# 04_MCU_Part.net
KiCad netlist of a schematic drawn in Altium Designer
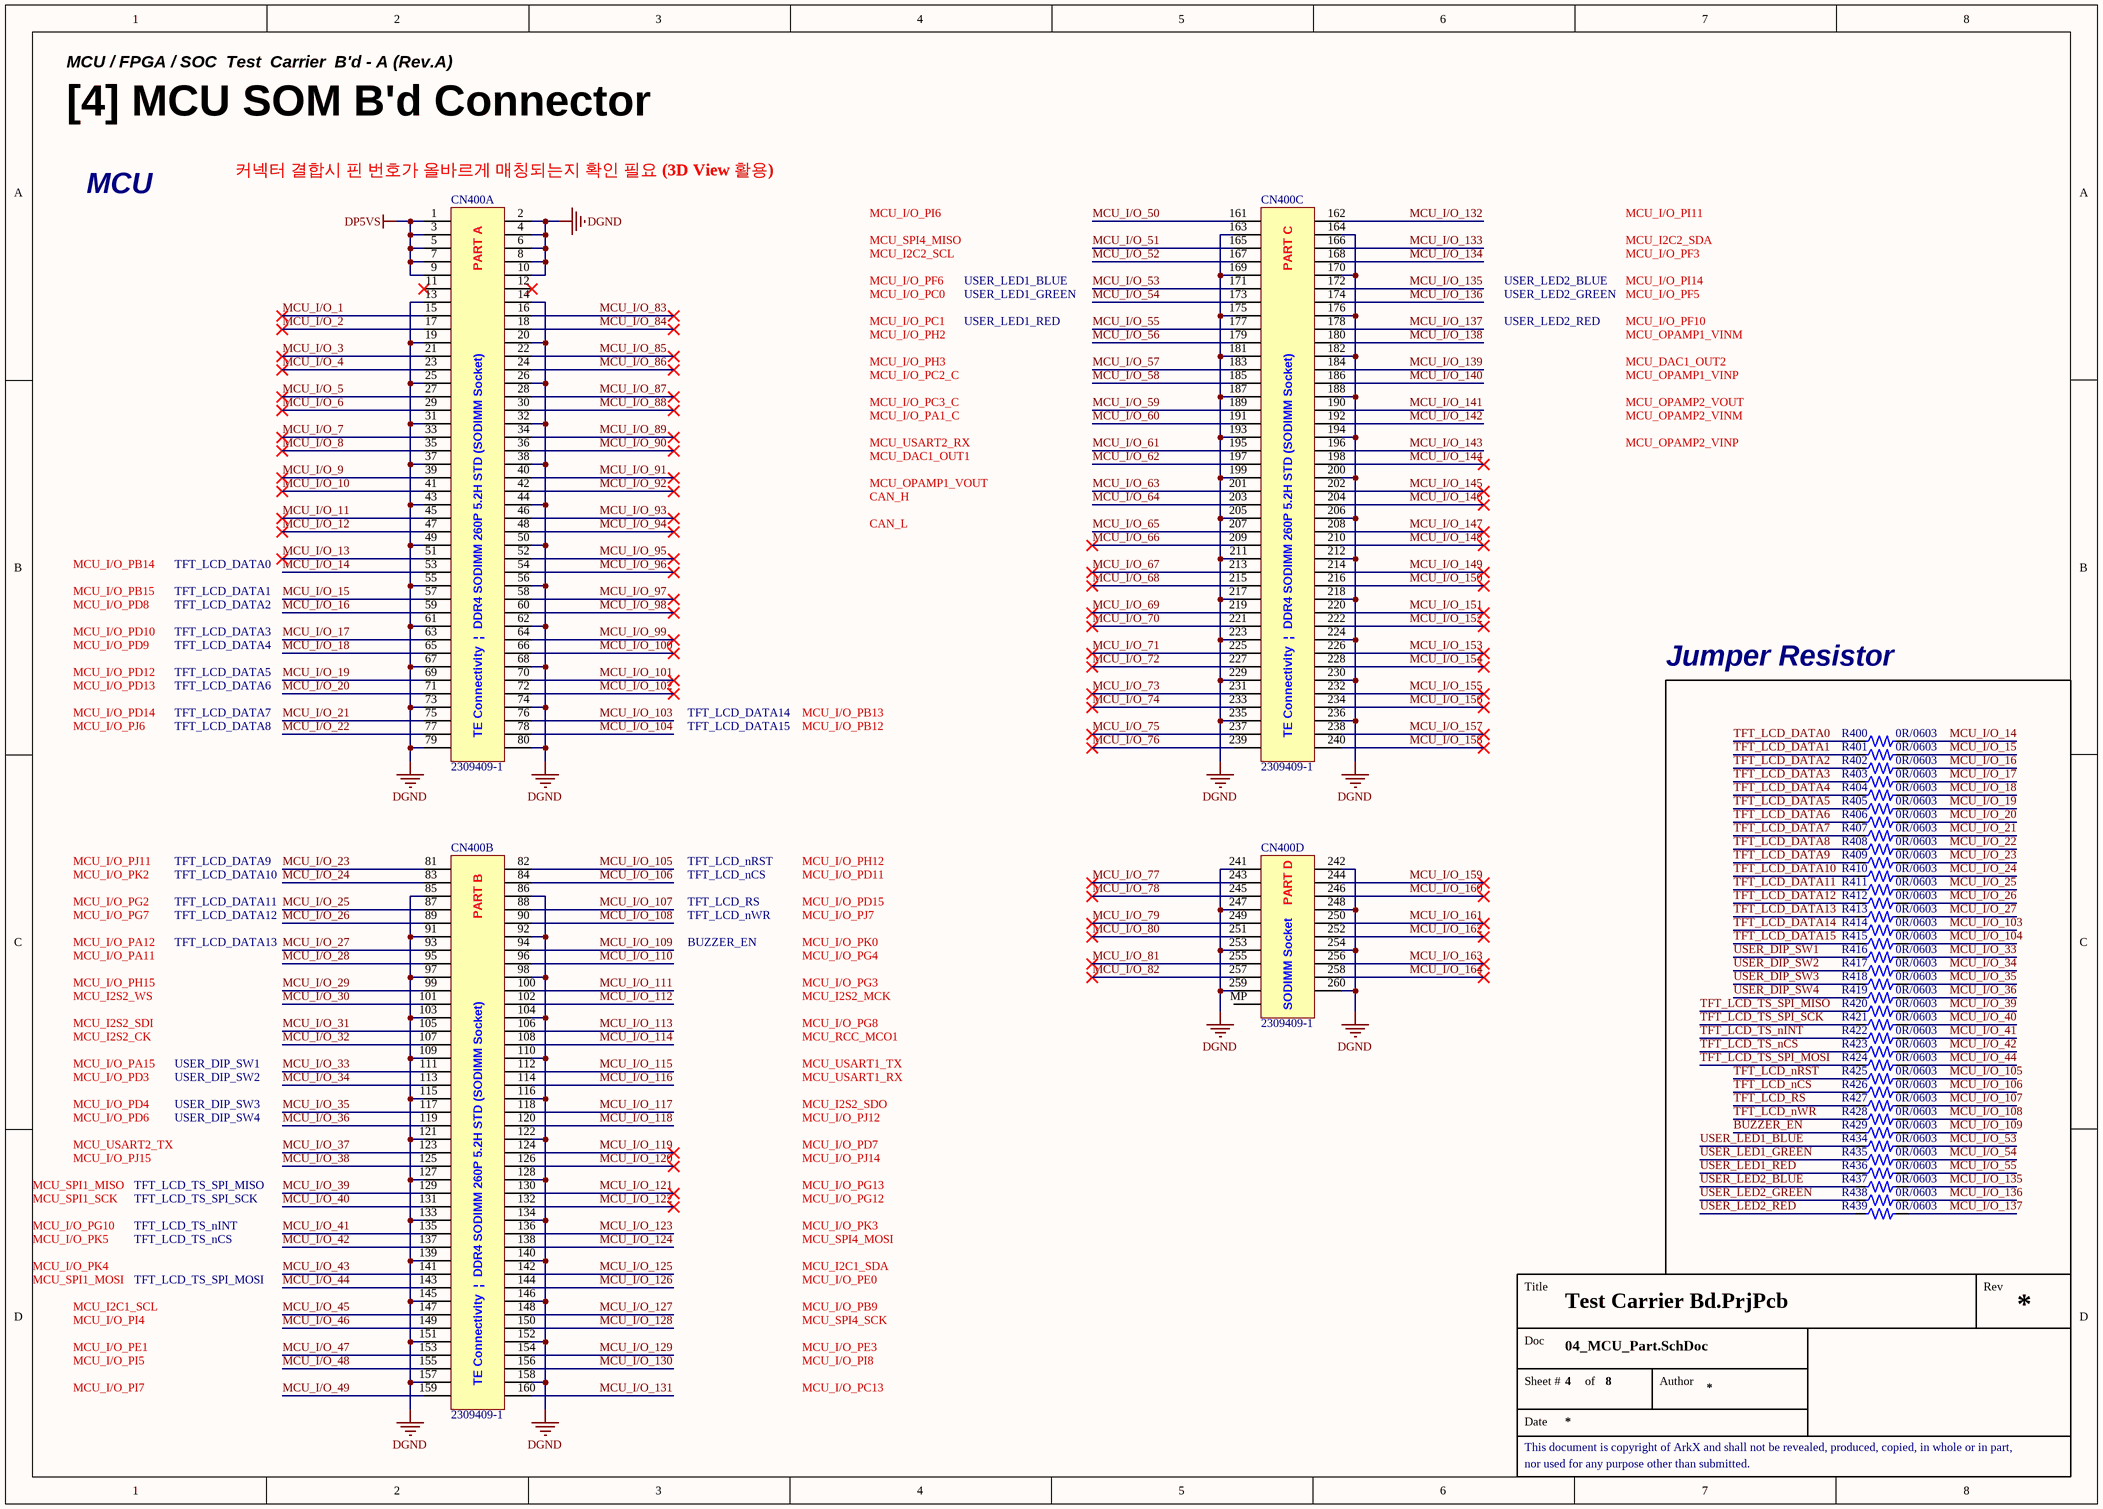
[diagram p0: 04_MCU_Part.SchDoc]

(export (version "E")
  (design (tool "Eeschema 10.0.6"))
  (components
    (comp (ref "CN400")
      (value "2309409-1")
      (footprint "CON_SODIMM_2309409-1")
      (fields (field (name "MANUFACTURER") "TE Connectivity") (field (name "LCSC PART #") "C5164025"))
      (libsource (lib "Arkx") (part "CON_SODIMM_2309409-1"))
    )
    (comp (ref "R400")
      (value "0R/0603")
      (footprint "RES 0603 (0201_inch)")
      (description "50mW Thick Film Resistors 25V ±1% 0Ω 0201  Chip Resistor - Surface Mount ROHS")
      (fields (field (name "LCSC PART #") "C106227"))
      (libsource (lib "Arkx") (part "RES_0R/0603/50mW"))
    )
    (comp (ref "R401")
      (value "0R/0603")
      (footprint "RES 0603 (0201_inch)")
      (description "50mW Thick Film Resistors 25V ±1% 0Ω 0201  Chip Resistor - Surface Mount ROHS")
      (fields (field (name "LCSC PART #") "C106227"))
      (libsource (lib "Arkx") (part "RES_0R/0603/50mW"))
    )
    (comp (ref "R402")
      (value "0R/0603")
      (footprint "RES 0603 (0201_inch)")
      (description "50mW Thick Film Resistors 25V ±1% 0Ω 0201  Chip Resistor - Surface Mount ROHS")
      (fields (field (name "LCSC PART #") "C106227"))
      (libsource (lib "Arkx") (part "RES_0R/0603/50mW"))
    )
    (comp (ref "R403")
      (value "0R/0603")
      (footprint "RES 0603 (0201_inch)")
      (description "50mW Thick Film Resistors 25V ±1% 0Ω 0201  Chip Resistor - Surface Mount ROHS")
      (fields (field (name "LCSC PART #") "C106227"))
      (libsource (lib "Arkx") (part "RES_0R/0603/50mW"))
    )
    (comp (ref "R404")
      (value "0R/0603")
      (footprint "RES 0603 (0201_inch)")
      (description "50mW Thick Film Resistors 25V ±1% 0Ω 0201  Chip Resistor - Surface Mount ROHS")
      (fields (field (name "LCSC PART #") "C106227"))
      (libsource (lib "Arkx") (part "RES_0R/0603/50mW"))
    )
    (comp (ref "R405")
      (value "0R/0603")
      (footprint "RES 0603 (0201_inch)")
      (description "50mW Thick Film Resistors 25V ±1% 0Ω 0201  Chip Resistor - Surface Mount ROHS")
      (fields (field (name "LCSC PART #") "C106227"))
      (libsource (lib "Arkx") (part "RES_0R/0603/50mW"))
    )
    (comp (ref "R406")
      (value "0R/0603")
      (footprint "RES 0603 (0201_inch)")
      (description "50mW Thick Film Resistors 25V ±1% 0Ω 0201  Chip Resistor - Surface Mount ROHS")
      (fields (field (name "LCSC PART #") "C106227"))
      (libsource (lib "Arkx") (part "RES_0R/0603/50mW"))
    )
    (comp (ref "R407")
      (value "0R/0603")
      (footprint "RES 0603 (0201_inch)")
      (description "50mW Thick Film Resistors 25V ±1% 0Ω 0201  Chip Resistor - Surface Mount ROHS")
      (fields (field (name "LCSC PART #") "C106227"))
      (libsource (lib "Arkx") (part "RES_0R/0603/50mW"))
    )
    (comp (ref "R408")
      (value "0R/0603")
      (footprint "RES 0603 (0201_inch)")
      (description "50mW Thick Film Resistors 25V ±1% 0Ω 0201  Chip Resistor - Surface Mount ROHS")
      (fields (field (name "LCSC PART #") "C106227"))
      (libsource (lib "Arkx") (part "RES_0R/0603/50mW"))
    )
    (comp (ref "R409")
      (value "0R/0603")
      (footprint "RES 0603 (0201_inch)")
      (description "50mW Thick Film Resistors 25V ±1% 0Ω 0201  Chip Resistor - Surface Mount ROHS")
      (fields (field (name "LCSC PART #") "C106227"))
      (libsource (lib "Arkx") (part "RES_0R/0603/50mW"))
    )
    (comp (ref "R410")
      (value "0R/0603")
      (footprint "RES 0603 (0201_inch)")
      (description "50mW Thick Film Resistors 25V ±1% 0Ω 0201  Chip Resistor - Surface Mount ROHS")
      (fields (field (name "LCSC PART #") "C106227"))
      (libsource (lib "Arkx") (part "RES_0R/0603/50mW"))
    )
    (comp (ref "R411")
      (value "0R/0603")
      (footprint "RES 0603 (0201_inch)")
      (description "50mW Thick Film Resistors 25V ±1% 0Ω 0201  Chip Resistor - Surface Mount ROHS")
      (fields (field (name "LCSC PART #") "C106227"))
      (libsource (lib "Arkx") (part "RES_0R/0603/50mW"))
    )
    (comp (ref "R412")
      (value "0R/0603")
      (footprint "RES 0603 (0201_inch)")
      (description "50mW Thick Film Resistors 25V ±1% 0Ω 0201  Chip Resistor - Surface Mount ROHS")
      (fields (field (name "LCSC PART #") "C106227"))
      (libsource (lib "Arkx") (part "RES_0R/0603/50mW"))
    )
    (comp (ref "R413")
      (value "0R/0603")
      (footprint "RES 0603 (0201_inch)")
      (description "50mW Thick Film Resistors 25V ±1% 0Ω 0201  Chip Resistor - Surface Mount ROHS")
      (fields (field (name "LCSC PART #") "C106227"))
      (libsource (lib "Arkx") (part "RES_0R/0603/50mW"))
    )
    (comp (ref "R414")
      (value "0R/0603")
      (footprint "RES 0603 (0201_inch)")
      (description "50mW Thick Film Resistors 25V ±1% 0Ω 0201  Chip Resistor - Surface Mount ROHS")
      (fields (field (name "LCSC PART #") "C106227"))
      (libsource (lib "Arkx") (part "RES_0R/0603/50mW"))
    )
    (comp (ref "R415")
      (value "0R/0603")
      (footprint "RES 0603 (0201_inch)")
      (description "50mW Thick Film Resistors 25V ±1% 0Ω 0201  Chip Resistor - Surface Mount ROHS")
      (fields (field (name "LCSC PART #") "C106227"))
      (libsource (lib "Arkx") (part "RES_0R/0603/50mW"))
    )
    (comp (ref "R416")
      (value "0R/0603")
      (footprint "RES 0603 (0201_inch)")
      (description "50mW Thick Film Resistors 25V ±1% 0Ω 0201  Chip Resistor - Surface Mount ROHS")
      (fields (field (name "LCSC PART #") "C106227"))
      (libsource (lib "Arkx") (part "RES_0R/0603/50mW"))
    )
    (comp (ref "R417")
      (value "0R/0603")
      (footprint "RES 0603 (0201_inch)")
      (description "50mW Thick Film Resistors 25V ±1% 0Ω 0201  Chip Resistor - Surface Mount ROHS")
      (fields (field (name "LCSC PART #") "C106227"))
      (libsource (lib "Arkx") (part "RES_0R/0603/50mW"))
    )
    (comp (ref "R418")
      (value "0R/0603")
      (footprint "RES 0603 (0201_inch)")
      (description "50mW Thick Film Resistors 25V ±1% 0Ω 0201  Chip Resistor - Surface Mount ROHS")
      (fields (field (name "LCSC PART #") "C106227"))
      (libsource (lib "Arkx") (part "RES_0R/0603/50mW"))
    )
    (comp (ref "R419")
      (value "0R/0603")
      (footprint "RES 0603 (0201_inch)")
      (description "50mW Thick Film Resistors 25V ±1% 0Ω 0201  Chip Resistor - Surface Mount ROHS")
      (fields (field (name "LCSC PART #") "C106227"))
      (libsource (lib "Arkx") (part "RES_0R/0603/50mW"))
    )
    (comp (ref "R420")
      (value "0R/0603")
      (footprint "RES 0603 (0201_inch)")
      (description "50mW Thick Film Resistors 25V ±1% 0Ω 0201  Chip Resistor - Surface Mount ROHS")
      (fields (field (name "LCSC PART #") "C106227"))
      (libsource (lib "Arkx") (part "RES_0R/0603/50mW"))
    )
    (comp (ref "R421")
      (value "0R/0603")
      (footprint "RES 0603 (0201_inch)")
      (description "50mW Thick Film Resistors 25V ±1% 0Ω 0201  Chip Resistor - Surface Mount ROHS")
      (fields (field (name "LCSC PART #") "C106227"))
      (libsource (lib "Arkx") (part "RES_0R/0603/50mW"))
    )
    (comp (ref "R422")
      (value "0R/0603")
      (footprint "RES 0603 (0201_inch)")
      (description "50mW Thick Film Resistors 25V ±1% 0Ω 0201  Chip Resistor - Surface Mount ROHS")
      (fields (field (name "LCSC PART #") "C106227"))
      (libsource (lib "Arkx") (part "RES_0R/0603/50mW"))
    )
    (comp (ref "R423")
      (value "0R/0603")
      (footprint "RES 0603 (0201_inch)")
      (description "50mW Thick Film Resistors 25V ±1% 0Ω 0201  Chip Resistor - Surface Mount ROHS")
      (fields (field (name "LCSC PART #") "C106227"))
      (libsource (lib "Arkx") (part "RES_0R/0603/50mW"))
    )
    (comp (ref "R424")
      (value "0R/0603")
      (footprint "RES 0603 (0201_inch)")
      (description "50mW Thick Film Resistors 25V ±1% 0Ω 0201  Chip Resistor - Surface Mount ROHS")
      (fields (field (name "LCSC PART #") "C106227"))
      (libsource (lib "Arkx") (part "RES_0R/0603/50mW"))
    )
    (comp (ref "R425")
      (value "0R/0603")
      (footprint "RES 0603 (0201_inch)")
      (description "50mW Thick Film Resistors 25V ±1% 0Ω 0201  Chip Resistor - Surface Mount ROHS")
      (fields (field (name "LCSC PART #") "C106227"))
      (libsource (lib "Arkx") (part "RES_0R/0603/50mW"))
    )
    (comp (ref "R426")
      (value "0R/0603")
      (footprint "RES 0603 (0201_inch)")
      (description "50mW Thick Film Resistors 25V ±1% 0Ω 0201  Chip Resistor - Surface Mount ROHS")
      (fields (field (name "LCSC PART #") "C106227"))
      (libsource (lib "Arkx") (part "RES_0R/0603/50mW"))
    )
    (comp (ref "R427")
      (value "0R/0603")
      (footprint "RES 0603 (0201_inch)")
      (description "50mW Thick Film Resistors 25V ±1% 0Ω 0201  Chip Resistor - Surface Mount ROHS")
      (fields (field (name "LCSC PART #") "C106227"))
      (libsource (lib "Arkx") (part "RES_0R/0603/50mW"))
    )
    (comp (ref "R428")
      (value "0R/0603")
      (footprint "RES 0603 (0201_inch)")
      (description "50mW Thick Film Resistors 25V ±1% 0Ω 0201  Chip Resistor - Surface Mount ROHS")
      (fields (field (name "LCSC PART #") "C106227"))
      (libsource (lib "Arkx") (part "RES_0R/0603/50mW"))
    )
    (comp (ref "R429")
      (value "0R/0603")
      (footprint "RES 0603 (0201_inch)")
      (description "50mW Thick Film Resistors 25V ±1% 0Ω 0201  Chip Resistor - Surface Mount ROHS")
      (fields (field (name "LCSC PART #") "C106227"))
      (libsource (lib "Arkx") (part "RES_0R/0603/50mW"))
    )
    (comp (ref "R434")
      (value "0R/0603")
      (footprint "RES 0603 (0201_inch)")
      (description "50mW Thick Film Resistors 25V ±1% 0Ω 0201  Chip Resistor - Surface Mount ROHS")
      (fields (field (name "LCSC PART #") "C106227"))
      (libsource (lib "Arkx") (part "RES_0R/0603/50mW"))
    )
    (comp (ref "R435")
      (value "0R/0603")
      (footprint "RES 0603 (0201_inch)")
      (description "50mW Thick Film Resistors 25V ±1% 0Ω 0201  Chip Resistor - Surface Mount ROHS")
      (fields (field (name "LCSC PART #") "C106227"))
      (libsource (lib "Arkx") (part "RES_0R/0603/50mW"))
    )
    (comp (ref "R436")
      (value "0R/0603")
      (footprint "RES 0603 (0201_inch)")
      (description "50mW Thick Film Resistors 25V ±1% 0Ω 0201  Chip Resistor - Surface Mount ROHS")
      (fields (field (name "LCSC PART #") "C106227"))
      (libsource (lib "Arkx") (part "RES_0R/0603/50mW"))
    )
    (comp (ref "R437")
      (value "0R/0603")
      (footprint "RES 0603 (0201_inch)")
      (description "50mW Thick Film Resistors 25V ±1% 0Ω 0201  Chip Resistor - Surface Mount ROHS")
      (fields (field (name "LCSC PART #") "C106227"))
      (libsource (lib "Arkx") (part "RES_0R/0603/50mW"))
    )
    (comp (ref "R438")
      (value "0R/0603")
      (footprint "RES 0603 (0201_inch)")
      (description "50mW Thick Film Resistors 25V ±1% 0Ω 0201  Chip Resistor - Surface Mount ROHS")
      (fields (field (name "LCSC PART #") "C106227"))
      (libsource (lib "Arkx") (part "RES_0R/0603/50mW"))
    )
    (comp (ref "R439")
      (value "0R/0603")
      (footprint "RES 0603 (0201_inch)")
      (description "50mW Thick Film Resistors 25V ±1% 0Ω 0201  Chip Resistor - Surface Mount ROHS")
      (fields (field (name "LCSC PART #") "C106227"))
      (libsource (lib "Arkx") (part "RES_0R/0603/50mW"))
    )
  )
  (nets
    (net (code "1") (name "/BUZZER_EN") (class "Default")
      (node (ref "R429") (pin "1") (pinfunction "1_1") (pintype "passive"))
    )
    (net (code "2") (name "/MCU_I{slash}O_1") (class "Default")
      (node (ref "CN400") (pin "15") (pinfunction "15_15") (pintype "passive+no_connect"))
    )
    (net (code "3") (name "/MCU_I{slash}O_2") (class "Default")
      (node (ref "CN400") (pin "17") (pinfunction "17_17") (pintype "passive+no_connect"))
    )
    (net (code "4") (name "/MCU_I{slash}O_3") (class "Default")
      (node (ref "CN400") (pin "21") (pinfunction "21_21") (pintype "passive+no_connect"))
    )
    (net (code "5") (name "/MCU_I{slash}O_4") (class "Default")
      (node (ref "CN400") (pin "23") (pinfunction "23_23") (pintype "passive+no_connect"))
    )
    (net (code "6") (name "/MCU_I{slash}O_5") (class "Default")
      (node (ref "CN400") (pin "27") (pinfunction "27_27") (pintype "passive+no_connect"))
    )
    (net (code "7") (name "/MCU_I{slash}O_6") (class "Default")
      (node (ref "CN400") (pin "29") (pinfunction "29_29") (pintype "passive+no_connect"))
    )
    (net (code "8") (name "/MCU_I{slash}O_7") (class "Default")
      (node (ref "CN400") (pin "33") (pinfunction "33_33") (pintype "passive+no_connect"))
    )
    (net (code "9") (name "/MCU_I{slash}O_8") (class "Default")
      (node (ref "CN400") (pin "35") (pinfunction "35_35") (pintype "passive+no_connect"))
    )
    (net (code "10") (name "/MCU_I{slash}O_9") (class "Default")
      (node (ref "CN400") (pin "39") (pinfunction "39_39") (pintype "passive+no_connect"))
    )
    (net (code "11") (name "/MCU_I{slash}O_10") (class "Default")
      (node (ref "CN400") (pin "41") (pinfunction "41_41") (pintype "passive+no_connect"))
    )
    (net (code "12") (name "/MCU_I{slash}O_11") (class "Default")
      (node (ref "CN400") (pin "45") (pinfunction "45_45") (pintype "passive+no_connect"))
    )
    (net (code "13") (name "/MCU_I{slash}O_12") (class "Default")
      (node (ref "CN400") (pin "47") (pinfunction "47_47") (pintype "passive+no_connect"))
    )
    (net (code "14") (name "/MCU_I{slash}O_13") (class "Default")
      (node (ref "CN400") (pin "51") (pinfunction "51_51") (pintype "passive+no_connect"))
    )
    (net (code "15") (name "/MCU_I{slash}O_14") (class "Default")
      (node (ref "CN400") (pin "53") (pinfunction "53_53") (pintype "passive"))
      (node (ref "R400") (pin "2") (pinfunction "2_2") (pintype "passive"))
    )
    (net (code "16") (name "/MCU_I{slash}O_15") (class "Default")
      (node (ref "CN400") (pin "57") (pinfunction "57_57") (pintype "passive"))
      (node (ref "R401") (pin "2") (pinfunction "2_2") (pintype "passive"))
    )
    (net (code "17") (name "/MCU_I{slash}O_16") (class "Default")
      (node (ref "CN400") (pin "59") (pinfunction "59_59") (pintype "passive"))
      (node (ref "R402") (pin "2") (pinfunction "2_2") (pintype "passive"))
    )
    (net (code "18") (name "/MCU_I{slash}O_17") (class "Default")
      (node (ref "CN400") (pin "63") (pinfunction "63_63") (pintype "passive"))
      (node (ref "R403") (pin "2") (pinfunction "2_2") (pintype "passive"))
    )
    (net (code "19") (name "/MCU_I{slash}O_18") (class "Default")
      (node (ref "CN400") (pin "65") (pinfunction "65_65") (pintype "passive"))
      (node (ref "R404") (pin "2") (pinfunction "2_2") (pintype "passive"))
    )
    (net (code "20") (name "/MCU_I{slash}O_19") (class "Default")
      (node (ref "CN400") (pin "69") (pinfunction "69_69") (pintype "passive"))
      (node (ref "R405") (pin "2") (pinfunction "2_2") (pintype "passive"))
    )
    (net (code "21") (name "/MCU_I{slash}O_20") (class "Default")
      (node (ref "CN400") (pin "71") (pinfunction "71_71") (pintype "passive"))
      (node (ref "R406") (pin "2") (pinfunction "2_2") (pintype "passive"))
    )
    (net (code "22") (name "/MCU_I{slash}O_21") (class "Default")
      (node (ref "CN400") (pin "75") (pinfunction "75_75") (pintype "passive"))
      (node (ref "R407") (pin "2") (pinfunction "2_2") (pintype "passive"))
    )
    (net (code "23") (name "/MCU_I{slash}O_22") (class "Default")
      (node (ref "CN400") (pin "77") (pinfunction "77_77") (pintype "passive"))
      (node (ref "R408") (pin "2") (pinfunction "2_2") (pintype "passive"))
    )
    (net (code "24") (name "/MCU_I{slash}O_23") (class "Default")
      (node (ref "CN400") (pin "81") (pinfunction "81_81") (pintype "passive"))
      (node (ref "R409") (pin "2") (pinfunction "2_2") (pintype "passive"))
    )
    (net (code "25") (name "/MCU_I{slash}O_24") (class "Default")
      (node (ref "CN400") (pin "83") (pinfunction "83_83") (pintype "passive"))
      (node (ref "R410") (pin "2") (pinfunction "2_2") (pintype "passive"))
    )
    (net (code "26") (name "/MCU_I{slash}O_25") (class "Default")
      (node (ref "CN400") (pin "87") (pinfunction "87_87") (pintype "passive"))
      (node (ref "R411") (pin "2") (pinfunction "2_2") (pintype "passive"))
    )
    (net (code "27") (name "/MCU_I{slash}O_26") (class "Default")
      (node (ref "CN400") (pin "89") (pinfunction "89_89") (pintype "passive"))
      (node (ref "R412") (pin "2") (pinfunction "2_2") (pintype "passive"))
    )
    (net (code "28") (name "/MCU_I{slash}O_27") (class "Default")
      (node (ref "CN400") (pin "93") (pinfunction "93_93") (pintype "passive"))
      (node (ref "R413") (pin "2") (pinfunction "2_2") (pintype "passive"))
    )
    (net (code "29") (name "/MCU_I{slash}O_28") (class "Default")
      (node (ref "CN400") (pin "95") (pinfunction "95_95") (pintype "passive"))
    )
    (net (code "30") (name "/MCU_I{slash}O_29") (class "Default")
      (node (ref "CN400") (pin "99") (pinfunction "99_99") (pintype "passive"))
    )
    (net (code "31") (name "/MCU_I{slash}O_30") (class "Default")
      (node (ref "CN400") (pin "101") (pinfunction "101_101") (pintype "passive"))
    )
    (net (code "32") (name "/MCU_I{slash}O_31") (class "Default")
      (node (ref "CN400") (pin "105") (pinfunction "105_105") (pintype "passive"))
    )
    (net (code "33") (name "/MCU_I{slash}O_32") (class "Default")
      (node (ref "CN400") (pin "107") (pinfunction "107_107") (pintype "passive"))
    )
    (net (code "34") (name "/MCU_I{slash}O_33") (class "Default")
      (node (ref "CN400") (pin "111") (pinfunction "111_111") (pintype "passive"))
      (node (ref "R416") (pin "2") (pinfunction "2_2") (pintype "passive"))
    )
    (net (code "35") (name "/MCU_I{slash}O_34") (class "Default")
      (node (ref "CN400") (pin "113") (pinfunction "113_113") (pintype "passive"))
      (node (ref "R417") (pin "2") (pinfunction "2_2") (pintype "passive"))
    )
    (net (code "36") (name "/MCU_I{slash}O_35") (class "Default")
      (node (ref "CN400") (pin "117") (pinfunction "117_117") (pintype "passive"))
      (node (ref "R418") (pin "2") (pinfunction "2_2") (pintype "passive"))
    )
    (net (code "37") (name "/MCU_I{slash}O_36") (class "Default")
      (node (ref "CN400") (pin "119") (pinfunction "119_119") (pintype "passive"))
      (node (ref "R419") (pin "2") (pinfunction "2_2") (pintype "passive"))
    )
    (net (code "38") (name "/MCU_I{slash}O_37") (class "Default")
      (node (ref "CN400") (pin "123") (pinfunction "123_123") (pintype "passive"))
    )
    (net (code "39") (name "/MCU_I{slash}O_38") (class "Default")
      (node (ref "CN400") (pin "125") (pinfunction "125_125") (pintype "passive"))
    )
    (net (code "40") (name "/MCU_I{slash}O_39") (class "Default")
      (node (ref "CN400") (pin "129") (pinfunction "129_129") (pintype "passive"))
      (node (ref "R420") (pin "2") (pinfunction "2_2") (pintype "passive"))
    )
    (net (code "41") (name "/MCU_I{slash}O_40") (class "Default")
      (node (ref "CN400") (pin "131") (pinfunction "131_131") (pintype "passive"))
      (node (ref "R421") (pin "2") (pinfunction "2_2") (pintype "passive"))
    )
    (net (code "42") (name "/MCU_I{slash}O_41") (class "Default")
      (node (ref "CN400") (pin "135") (pinfunction "135_135") (pintype "passive"))
      (node (ref "R422") (pin "2") (pinfunction "2_2") (pintype "passive"))
    )
    (net (code "43") (name "/MCU_I{slash}O_42") (class "Default")
      (node (ref "CN400") (pin "137") (pinfunction "137_137") (pintype "passive"))
      (node (ref "R423") (pin "2") (pinfunction "2_2") (pintype "passive"))
    )
    (net (code "44") (name "/MCU_I{slash}O_43") (class "Default")
      (node (ref "CN400") (pin "141") (pinfunction "141_141") (pintype "passive"))
    )
    (net (code "45") (name "/MCU_I{slash}O_44") (class "Default")
      (node (ref "CN400") (pin "143") (pinfunction "143_143") (pintype "passive"))
      (node (ref "R424") (pin "2") (pinfunction "2_2") (pintype "passive"))
    )
    (net (code "46") (name "/MCU_I{slash}O_45") (class "Default")
      (node (ref "CN400") (pin "147") (pinfunction "147_147") (pintype "passive"))
    )
    (net (code "47") (name "/MCU_I{slash}O_46") (class "Default")
      (node (ref "CN400") (pin "149") (pinfunction "149_149") (pintype "passive"))
    )
    (net (code "48") (name "/MCU_I{slash}O_47") (class "Default")
      (node (ref "CN400") (pin "153") (pinfunction "153_153") (pintype "passive"))
    )
    (net (code "49") (name "/MCU_I{slash}O_48") (class "Default")
      (node (ref "CN400") (pin "155") (pinfunction "155_155") (pintype "passive"))
    )
    (net (code "50") (name "/MCU_I{slash}O_49") (class "Default")
      (node (ref "CN400") (pin "159") (pinfunction "159_159") (pintype "passive"))
    )
    (net (code "51") (name "/MCU_I{slash}O_50") (class "Default")
      (node (ref "CN400") (pin "161") (pinfunction "161_161") (pintype "passive"))
    )
    (net (code "52") (name "/MCU_I{slash}O_51") (class "Default")
      (node (ref "CN400") (pin "165") (pinfunction "165_165") (pintype "passive"))
    )
    (net (code "53") (name "/MCU_I{slash}O_52") (class "Default")
      (node (ref "CN400") (pin "167") (pinfunction "167_167") (pintype "passive"))
    )
    (net (code "54") (name "/MCU_I{slash}O_53") (class "Default")
      (node (ref "CN400") (pin "171") (pinfunction "171_171") (pintype "passive"))
      (node (ref "R434") (pin "2") (pinfunction "2_2") (pintype "passive"))
    )
    (net (code "55") (name "/MCU_I{slash}O_54") (class "Default")
      (node (ref "CN400") (pin "173") (pinfunction "173_173") (pintype "passive"))
      (node (ref "R435") (pin "2") (pinfunction "2_2") (pintype "passive"))
    )
    (net (code "56") (name "/MCU_I{slash}O_55") (class "Default")
      (node (ref "CN400") (pin "177") (pinfunction "177_177") (pintype "passive"))
      (node (ref "R436") (pin "2") (pinfunction "2_2") (pintype "passive"))
    )
    (net (code "57") (name "/MCU_I{slash}O_56") (class "Default")
      (node (ref "CN400") (pin "179") (pinfunction "179_179") (pintype "passive"))
    )
    (net (code "58") (name "/MCU_I{slash}O_57") (class "Default")
      (node (ref "CN400") (pin "183") (pinfunction "183_183") (pintype "passive"))
    )
    (net (code "59") (name "/MCU_I{slash}O_58") (class "Default")
      (node (ref "CN400") (pin "185") (pinfunction "185_185") (pintype "passive"))
    )
    (net (code "60") (name "/MCU_I{slash}O_59") (class "Default")
      (node (ref "CN400") (pin "189") (pinfunction "189_189") (pintype "passive"))
    )
    (net (code "61") (name "/MCU_I{slash}O_60") (class "Default")
      (node (ref "CN400") (pin "191") (pinfunction "191_191") (pintype "passive"))
    )
    (net (code "62") (name "/MCU_I{slash}O_61") (class "Default")
      (node (ref "CN400") (pin "195") (pinfunction "195_195") (pintype "passive"))
    )
    (net (code "63") (name "/MCU_I{slash}O_62") (class "Default")
      (node (ref "CN400") (pin "197") (pinfunction "197_197") (pintype "passive"))
    )
    (net (code "64") (name "/MCU_I{slash}O_63") (class "Default")
      (node (ref "CN400") (pin "201") (pinfunction "201_201") (pintype "passive"))
    )
    (net (code "65") (name "/MCU_I{slash}O_64") (class "Default")
      (node (ref "CN400") (pin "203") (pinfunction "203_203") (pintype "passive"))
    )
    (net (code "66") (name "/MCU_I{slash}O_65") (class "Default")
      (node (ref "CN400") (pin "207") (pinfunction "207_207") (pintype "passive"))
    )
    (net (code "67") (name "/MCU_I{slash}O_66") (class "Default")
      (node (ref "CN400") (pin "209") (pinfunction "209_209") (pintype "passive+no_connect"))
    )
    (net (code "68") (name "/MCU_I{slash}O_67") (class "Default")
      (node (ref "CN400") (pin "213") (pinfunction "213_213") (pintype "passive+no_connect"))
    )
    (net (code "69") (name "/MCU_I{slash}O_68") (class "Default")
      (node (ref "CN400") (pin "215") (pinfunction "215_215") (pintype "passive+no_connect"))
    )
    (net (code "70") (name "/MCU_I{slash}O_69") (class "Default")
      (node (ref "CN400") (pin "219") (pinfunction "219_219") (pintype "passive+no_connect"))
    )
    (net (code "71") (name "/MCU_I{slash}O_70") (class "Default")
      (node (ref "CN400") (pin "221") (pinfunction "221_221") (pintype "passive+no_connect"))
    )
    (net (code "72") (name "/MCU_I{slash}O_71") (class "Default")
      (node (ref "CN400") (pin "225") (pinfunction "225_225") (pintype "passive+no_connect"))
    )
    (net (code "73") (name "/MCU_I{slash}O_72") (class "Default")
      (node (ref "CN400") (pin "227") (pinfunction "227_227") (pintype "passive+no_connect"))
    )
    (net (code "74") (name "/MCU_I{slash}O_73") (class "Default")
      (node (ref "CN400") (pin "231") (pinfunction "231_231") (pintype "passive+no_connect"))
    )
    (net (code "75") (name "/MCU_I{slash}O_74") (class "Default")
      (node (ref "CN400") (pin "233") (pinfunction "233_233") (pintype "passive+no_connect"))
    )
    (net (code "76") (name "/MCU_I{slash}O_75") (class "Default")
      (node (ref "CN400") (pin "237") (pinfunction "237_237") (pintype "passive+no_connect"))
    )
    (net (code "77") (name "/MCU_I{slash}O_76") (class "Default")
      (node (ref "CN400") (pin "239") (pinfunction "239_239") (pintype "passive+no_connect"))
    )
    (net (code "78") (name "/MCU_I{slash}O_77") (class "Default")
      (node (ref "CN400") (pin "243") (pinfunction "243_243") (pintype "passive+no_connect"))
    )
    (net (code "79") (name "/MCU_I{slash}O_78") (class "Default")
      (node (ref "CN400") (pin "245") (pinfunction "245_245") (pintype "passive+no_connect"))
    )
    (net (code "80") (name "/MCU_I{slash}O_79") (class "Default")
      (node (ref "CN400") (pin "249") (pinfunction "249_249") (pintype "passive+no_connect"))
    )
    (net (code "81") (name "/MCU_I{slash}O_80") (class "Default")
      (node (ref "CN400") (pin "251") (pinfunction "251_251") (pintype "passive+no_connect"))
    )
    (net (code "82") (name "/MCU_I{slash}O_81") (class "Default")
      (node (ref "CN400") (pin "255") (pinfunction "255_255") (pintype "passive+no_connect"))
    )
    (net (code "83") (name "/MCU_I{slash}O_82") (class "Default")
      (node (ref "CN400") (pin "257") (pinfunction "257_257") (pintype "passive+no_connect"))
    )
    (net (code "84") (name "/MCU_I{slash}O_83") (class "Default")
      (node (ref "CN400") (pin "16") (pinfunction "16_16") (pintype "passive+no_connect"))
    )
    (net (code "85") (name "/MCU_I{slash}O_84") (class "Default")
      (node (ref "CN400") (pin "18") (pinfunction "18_18") (pintype "passive+no_connect"))
    )
    (net (code "86") (name "/MCU_I{slash}O_85") (class "Default")
      (node (ref "CN400") (pin "22") (pinfunction "22_22") (pintype "passive+no_connect"))
    )
    (net (code "87") (name "/MCU_I{slash}O_86") (class "Default")
      (node (ref "CN400") (pin "24") (pinfunction "24_24") (pintype "passive+no_connect"))
    )
    (net (code "88") (name "/MCU_I{slash}O_87") (class "Default")
      (node (ref "CN400") (pin "28") (pinfunction "28_28") (pintype "passive+no_connect"))
    )
    (net (code "89") (name "/MCU_I{slash}O_88") (class "Default")
      (node (ref "CN400") (pin "30") (pinfunction "30_30") (pintype "passive+no_connect"))
    )
    (net (code "90") (name "/MCU_I{slash}O_89") (class "Default")
      (node (ref "CN400") (pin "34") (pinfunction "34_34") (pintype "passive+no_connect"))
    )
    (net (code "91") (name "/MCU_I{slash}O_90") (class "Default")
      (node (ref "CN400") (pin "36") (pinfunction "36_36") (pintype "passive+no_connect"))
    )
    (net (code "92") (name "/MCU_I{slash}O_91") (class "Default")
      (node (ref "CN400") (pin "40") (pinfunction "40_40") (pintype "passive+no_connect"))
    )
    (net (code "93") (name "/MCU_I{slash}O_92") (class "Default")
      (node (ref "CN400") (pin "42") (pinfunction "42_42") (pintype "passive+no_connect"))
    )
    (net (code "94") (name "/MCU_I{slash}O_93") (class "Default")
      (node (ref "CN400") (pin "46") (pinfunction "46_46") (pintype "passive+no_connect"))
    )
    (net (code "95") (name "/MCU_I{slash}O_94") (class "Default")
      (node (ref "CN400") (pin "48") (pinfunction "48_48") (pintype "passive+no_connect"))
    )
    (net (code "96") (name "/MCU_I{slash}O_95") (class "Default")
      (node (ref "CN400") (pin "52") (pinfunction "52_52") (pintype "passive+no_connect"))
    )
    (net (code "97") (name "/MCU_I{slash}O_96") (class "Default")
      (node (ref "CN400") (pin "54") (pinfunction "54_54") (pintype "passive+no_connect"))
    )
    (net (code "98") (name "/MCU_I{slash}O_97") (class "Default")
      (node (ref "CN400") (pin "58") (pinfunction "58_58") (pintype "passive+no_connect"))
    )
    (net (code "99") (name "/MCU_I{slash}O_98") (class "Default")
      (node (ref "CN400") (pin "60") (pinfunction "60_60") (pintype "passive+no_connect"))
    )
    (net (code "100") (name "/MCU_I{slash}O_99") (class "Default")
      (node (ref "CN400") (pin "64") (pinfunction "64_64") (pintype "passive+no_connect"))
    )
    (net (code "101") (name "/MCU_I{slash}O_100") (class "Default")
      (node (ref "CN400") (pin "66") (pinfunction "66_66") (pintype "passive+no_connect"))
    )
    (net (code "102") (name "/MCU_I{slash}O_101") (class "Default")
      (node (ref "CN400") (pin "70") (pinfunction "70_70") (pintype "passive+no_connect"))
    )
    (net (code "103") (name "/MCU_I{slash}O_102") (class "Default")
      (node (ref "CN400") (pin "72") (pinfunction "72_72") (pintype "passive+no_connect"))
    )
    (net (code "104") (name "/MCU_I{slash}O_103") (class "Default")
      (node (ref "CN400") (pin "76") (pinfunction "76_76") (pintype "passive"))
      (node (ref "R414") (pin "2") (pinfunction "2_2") (pintype "passive"))
    )
    (net (code "105") (name "/MCU_I{slash}O_104") (class "Default")
      (node (ref "CN400") (pin "78") (pinfunction "78_78") (pintype "passive"))
      (node (ref "R415") (pin "2") (pinfunction "2_2") (pintype "passive"))
    )
    (net (code "106") (name "/MCU_I{slash}O_105") (class "Default")
      (node (ref "CN400") (pin "82") (pinfunction "82_82") (pintype "passive"))
      (node (ref "R425") (pin "2") (pinfunction "2_2") (pintype "passive"))
    )
    (net (code "107") (name "/MCU_I{slash}O_106") (class "Default")
      (node (ref "CN400") (pin "84") (pinfunction "84_84") (pintype "passive"))
      (node (ref "R426") (pin "2") (pinfunction "2_2") (pintype "passive"))
    )
    (net (code "108") (name "/MCU_I{slash}O_107") (class "Default")
      (node (ref "CN400") (pin "88") (pinfunction "88_88") (pintype "passive"))
      (node (ref "R427") (pin "2") (pinfunction "2_2") (pintype "passive"))
    )
    (net (code "109") (name "/MCU_I{slash}O_108") (class "Default")
      (node (ref "CN400") (pin "90") (pinfunction "90_90") (pintype "passive"))
      (node (ref "R428") (pin "2") (pinfunction "2_2") (pintype "passive"))
    )
    (net (code "110") (name "/MCU_I{slash}O_109") (class "Default")
      (node (ref "CN400") (pin "94") (pinfunction "94_94") (pintype "passive"))
      (node (ref "R429") (pin "2") (pinfunction "2_2") (pintype "passive"))
    )
    (net (code "111") (name "/MCU_I{slash}O_110") (class "Default")
      (node (ref "CN400") (pin "96") (pinfunction "96_96") (pintype "passive"))
    )
    (net (code "112") (name "/MCU_I{slash}O_111") (class "Default")
      (node (ref "CN400") (pin "100") (pinfunction "100_100") (pintype "passive"))
    )
    (net (code "113") (name "/MCU_I{slash}O_112") (class "Default")
      (node (ref "CN400") (pin "102") (pinfunction "102_102") (pintype "passive"))
    )
    (net (code "114") (name "/MCU_I{slash}O_113") (class "Default")
      (node (ref "CN400") (pin "106") (pinfunction "106_106") (pintype "passive"))
    )
    (net (code "115") (name "/MCU_I{slash}O_114") (class "Default")
      (node (ref "CN400") (pin "108") (pinfunction "108_108") (pintype "passive"))
    )
    (net (code "116") (name "/MCU_I{slash}O_115") (class "Default")
      (node (ref "CN400") (pin "112") (pinfunction "112_112") (pintype "passive"))
    )
    (net (code "117") (name "/MCU_I{slash}O_116") (class "Default")
      (node (ref "CN400") (pin "114") (pinfunction "114_114") (pintype "passive"))
    )
    (net (code "118") (name "/MCU_I{slash}O_117") (class "Default")
      (node (ref "CN400") (pin "118") (pinfunction "118_118") (pintype "passive"))
    )
    (net (code "119") (name "/MCU_I{slash}O_118") (class "Default")
      (node (ref "CN400") (pin "120") (pinfunction "120_120") (pintype "passive"))
    )
    (net (code "120") (name "/MCU_I{slash}O_119") (class "Default")
      (node (ref "CN400") (pin "124") (pinfunction "124_124") (pintype "passive+no_connect"))
    )
    (net (code "121") (name "/MCU_I{slash}O_120") (class "Default")
      (node (ref "CN400") (pin "126") (pinfunction "126_126") (pintype "passive+no_connect"))
    )
    (net (code "122") (name "/MCU_I{slash}O_121") (class "Default")
      (node (ref "CN400") (pin "130") (pinfunction "130_130") (pintype "passive+no_connect"))
    )
    (net (code "123") (name "/MCU_I{slash}O_122") (class "Default")
      (node (ref "CN400") (pin "132") (pinfunction "132_132") (pintype "passive+no_connect"))
    )
    (net (code "124") (name "/MCU_I{slash}O_123") (class "Default")
      (node (ref "CN400") (pin "136") (pinfunction "136_136") (pintype "passive"))
    )
    (net (code "125") (name "/MCU_I{slash}O_124") (class "Default")
      (node (ref "CN400") (pin "138") (pinfunction "138_138") (pintype "passive"))
    )
    (net (code "126") (name "/MCU_I{slash}O_125") (class "Default")
      (node (ref "CN400") (pin "142") (pinfunction "142_142") (pintype "passive"))
    )
    (net (code "127") (name "/MCU_I{slash}O_126") (class "Default")
      (node (ref "CN400") (pin "144") (pinfunction "144_144") (pintype "passive"))
    )
    (net (code "128") (name "/MCU_I{slash}O_127") (class "Default")
      (node (ref "CN400") (pin "148") (pinfunction "148_148") (pintype "passive"))
    )
    (net (code "129") (name "/MCU_I{slash}O_128") (class "Default")
      (node (ref "CN400") (pin "150") (pinfunction "150_150") (pintype "passive"))
    )
    (net (code "130") (name "/MCU_I{slash}O_129") (class "Default")
      (node (ref "CN400") (pin "154") (pinfunction "154_154") (pintype "passive"))
    )
    (net (code "131") (name "/MCU_I{slash}O_130") (class "Default")
      (node (ref "CN400") (pin "156") (pinfunction "156_156") (pintype "passive"))
    )
    (net (code "132") (name "/MCU_I{slash}O_131") (class "Default")
      (node (ref "CN400") (pin "160") (pinfunction "160_160") (pintype "passive"))
    )
    (net (code "133") (name "/MCU_I{slash}O_132") (class "Default")
      (node (ref "CN400") (pin "162") (pinfunction "162_162") (pintype "passive"))
    )
    (net (code "134") (name "/MCU_I{slash}O_133") (class "Default")
      (node (ref "CN400") (pin "166") (pinfunction "166_166") (pintype "passive"))
    )
    (net (code "135") (name "/MCU_I{slash}O_134") (class "Default")
      (node (ref "CN400") (pin "168") (pinfunction "168_168") (pintype "passive"))
    )
    (net (code "136") (name "/MCU_I{slash}O_135") (class "Default")
      (node (ref "CN400") (pin "172") (pinfunction "172_172") (pintype "passive"))
      (node (ref "R437") (pin "2") (pinfunction "2_2") (pintype "passive"))
    )
    (net (code "137") (name "/MCU_I{slash}O_136") (class "Default")
      (node (ref "CN400") (pin "174") (pinfunction "174_174") (pintype "passive"))
      (node (ref "R438") (pin "2") (pinfunction "2_2") (pintype "passive"))
    )
    (net (code "138") (name "/MCU_I{slash}O_137") (class "Default")
      (node (ref "CN400") (pin "178") (pinfunction "178_178") (pintype "passive"))
      (node (ref "R439") (pin "2") (pinfunction "2_2") (pintype "passive"))
    )
    (net (code "139") (name "/MCU_I{slash}O_138") (class "Default")
      (node (ref "CN400") (pin "180") (pinfunction "180_180") (pintype "passive"))
    )
    (net (code "140") (name "/MCU_I{slash}O_139") (class "Default")
      (node (ref "CN400") (pin "184") (pinfunction "184_184") (pintype "passive"))
    )
    (net (code "141") (name "/MCU_I{slash}O_140") (class "Default")
      (node (ref "CN400") (pin "186") (pinfunction "186_186") (pintype "passive"))
    )
    (net (code "142") (name "/MCU_I{slash}O_141") (class "Default")
      (node (ref "CN400") (pin "190") (pinfunction "190_190") (pintype "passive"))
    )
    (net (code "143") (name "/MCU_I{slash}O_142") (class "Default")
      (node (ref "CN400") (pin "192") (pinfunction "192_192") (pintype "passive"))
    )
    (net (code "144") (name "/MCU_I{slash}O_143") (class "Default")
      (node (ref "CN400") (pin "196") (pinfunction "196_196") (pintype "passive"))
    )
    (net (code "145") (name "/MCU_I{slash}O_144") (class "Default")
      (node (ref "CN400") (pin "198") (pinfunction "198_198") (pintype "passive+no_connect"))
    )
    (net (code "146") (name "/MCU_I{slash}O_145") (class "Default")
      (node (ref "CN400") (pin "202") (pinfunction "202_202") (pintype "passive+no_connect"))
    )
    (net (code "147") (name "/MCU_I{slash}O_146") (class "Default")
      (node (ref "CN400") (pin "204") (pinfunction "204_204") (pintype "passive+no_connect"))
    )
    (net (code "148") (name "/MCU_I{slash}O_147") (class "Default")
      (node (ref "CN400") (pin "208") (pinfunction "208_208") (pintype "passive+no_connect"))
    )
    (net (code "149") (name "/MCU_I{slash}O_148") (class "Default")
      (node (ref "CN400") (pin "210") (pinfunction "210_210") (pintype "passive+no_connect"))
    )
    (net (code "150") (name "/MCU_I{slash}O_149") (class "Default")
      (node (ref "CN400") (pin "214") (pinfunction "214_214") (pintype "passive+no_connect"))
    )
    (net (code "151") (name "/MCU_I{slash}O_150") (class "Default")
      (node (ref "CN400") (pin "216") (pinfunction "216_216") (pintype "passive+no_connect"))
    )
    (net (code "152") (name "/MCU_I{slash}O_151") (class "Default")
      (node (ref "CN400") (pin "220") (pinfunction "220_220") (pintype "passive+no_connect"))
    )
    (net (code "153") (name "/MCU_I{slash}O_152") (class "Default")
      (node (ref "CN400") (pin "222") (pinfunction "222_222") (pintype "passive+no_connect"))
    )
    (net (code "154") (name "/MCU_I{slash}O_153") (class "Default")
      (node (ref "CN400") (pin "226") (pinfunction "226_226") (pintype "passive+no_connect"))
    )
    (net (code "155") (name "/MCU_I{slash}O_154") (class "Default")
      (node (ref "CN400") (pin "228") (pinfunction "228_228") (pintype "passive+no_connect"))
    )
    (net (code "156") (name "/MCU_I{slash}O_155") (class "Default")
      (node (ref "CN400") (pin "232") (pinfunction "232_232") (pintype "passive+no_connect"))
    )
    (net (code "157") (name "/MCU_I{slash}O_156") (class "Default")
      (node (ref "CN400") (pin "234") (pinfunction "234_234") (pintype "passive+no_connect"))
    )
    (net (code "158") (name "/MCU_I{slash}O_157") (class "Default")
      (node (ref "CN400") (pin "238") (pinfunction "238_238") (pintype "passive+no_connect"))
    )
    (net (code "159") (name "/MCU_I{slash}O_158") (class "Default")
      (node (ref "CN400") (pin "240") (pinfunction "240_240") (pintype "passive+no_connect"))
    )
    (net (code "160") (name "/MCU_I{slash}O_159") (class "Default")
      (node (ref "CN400") (pin "244") (pinfunction "244_244") (pintype "passive+no_connect"))
    )
    (net (code "161") (name "/MCU_I{slash}O_160") (class "Default")
      (node (ref "CN400") (pin "246") (pinfunction "246_246") (pintype "passive+no_connect"))
    )
    (net (code "162") (name "/MCU_I{slash}O_161") (class "Default")
      (node (ref "CN400") (pin "250") (pinfunction "250_250") (pintype "passive+no_connect"))
    )
    (net (code "163") (name "/MCU_I{slash}O_162") (class "Default")
      (node (ref "CN400") (pin "252") (pinfunction "252_252") (pintype "passive+no_connect"))
    )
    (net (code "164") (name "/MCU_I{slash}O_163") (class "Default")
      (node (ref "CN400") (pin "256") (pinfunction "256_256") (pintype "passive+no_connect"))
    )
    (net (code "165") (name "/MCU_I{slash}O_164") (class "Default")
      (node (ref "CN400") (pin "258") (pinfunction "258_258") (pintype "passive+no_connect"))
    )
    (net (code "166") (name "/TFT_LCD_DATA0") (class "Default")
      (node (ref "R400") (pin "1") (pinfunction "1_1") (pintype "passive"))
    )
    (net (code "167") (name "/TFT_LCD_DATA1") (class "Default")
      (node (ref "R401") (pin "1") (pinfunction "1_1") (pintype "passive"))
    )
    (net (code "168") (name "/TFT_LCD_DATA2") (class "Default")
      (node (ref "R402") (pin "1") (pinfunction "1_1") (pintype "passive"))
    )
    (net (code "169") (name "/TFT_LCD_DATA3") (class "Default")
      (node (ref "R403") (pin "1") (pinfunction "1_1") (pintype "passive"))
    )
    (net (code "170") (name "/TFT_LCD_DATA4") (class "Default")
      (node (ref "R404") (pin "1") (pinfunction "1_1") (pintype "passive"))
    )
    (net (code "171") (name "/TFT_LCD_DATA5") (class "Default")
      (node (ref "R405") (pin "1") (pinfunction "1_1") (pintype "passive"))
    )
    (net (code "172") (name "/TFT_LCD_DATA6") (class "Default")
      (node (ref "R406") (pin "1") (pinfunction "1_1") (pintype "passive"))
    )
    (net (code "173") (name "/TFT_LCD_DATA7") (class "Default")
      (node (ref "R407") (pin "1") (pinfunction "1_1") (pintype "passive"))
    )
    (net (code "174") (name "/TFT_LCD_DATA8") (class "Default")
      (node (ref "R408") (pin "1") (pinfunction "1_1") (pintype "passive"))
    )
    (net (code "175") (name "/TFT_LCD_DATA9") (class "Default")
      (node (ref "R409") (pin "1") (pinfunction "1_1") (pintype "passive"))
    )
    (net (code "176") (name "/TFT_LCD_DATA10") (class "Default")
      (node (ref "R410") (pin "1") (pinfunction "1_1") (pintype "passive"))
    )
    (net (code "177") (name "/TFT_LCD_DATA11") (class "Default")
      (node (ref "R411") (pin "1") (pinfunction "1_1") (pintype "passive"))
    )
    (net (code "178") (name "/TFT_LCD_DATA12") (class "Default")
      (node (ref "R412") (pin "1") (pinfunction "1_1") (pintype "passive"))
    )
    (net (code "179") (name "/TFT_LCD_DATA13") (class "Default")
      (node (ref "R413") (pin "1") (pinfunction "1_1") (pintype "passive"))
    )
    (net (code "180") (name "/TFT_LCD_DATA14") (class "Default")
      (node (ref "R414") (pin "1") (pinfunction "1_1") (pintype "passive"))
    )
    (net (code "181") (name "/TFT_LCD_DATA15") (class "Default")
      (node (ref "R415") (pin "1") (pinfunction "1_1") (pintype "passive"))
    )
    (net (code "182") (name "/TFT_LCD_RS") (class "Default")
      (node (ref "R427") (pin "1") (pinfunction "1_1") (pintype "passive"))
    )
    (net (code "183") (name "/TFT_LCD_TS_SPI_MISO") (class "Default")
      (node (ref "R420") (pin "1") (pinfunction "1_1") (pintype "passive"))
    )
    (net (code "184") (name "/TFT_LCD_TS_SPI_MOSI") (class "Default")
      (node (ref "R424") (pin "1") (pinfunction "1_1") (pintype "passive"))
    )
    (net (code "185") (name "/TFT_LCD_TS_SPI_SCK") (class "Default")
      (node (ref "R421") (pin "1") (pinfunction "1_1") (pintype "passive"))
    )
    (net (code "186") (name "/TFT_LCD_TS_nCS") (class "Default")
      (node (ref "R423") (pin "1") (pinfunction "1_1") (pintype "passive"))
    )
    (net (code "187") (name "/TFT_LCD_TS_nINT") (class "Default")
      (node (ref "R422") (pin "1") (pinfunction "1_1") (pintype "passive"))
    )
    (net (code "188") (name "/TFT_LCD_nCS") (class "Default")
      (node (ref "R426") (pin "1") (pinfunction "1_1") (pintype "passive"))
    )
    (net (code "189") (name "/TFT_LCD_nRST") (class "Default")
      (node (ref "R425") (pin "1") (pinfunction "1_1") (pintype "passive"))
    )
    (net (code "190") (name "/TFT_LCD_nWR") (class "Default")
      (node (ref "R428") (pin "1") (pinfunction "1_1") (pintype "passive"))
    )
    (net (code "191") (name "/USER_DIP_SW1") (class "Default")
      (node (ref "R416") (pin "1") (pinfunction "1_1") (pintype "passive"))
    )
    (net (code "192") (name "/USER_DIP_SW2") (class "Default")
      (node (ref "R417") (pin "1") (pinfunction "1_1") (pintype "passive"))
    )
    (net (code "193") (name "/USER_DIP_SW3") (class "Default")
      (node (ref "R418") (pin "1") (pinfunction "1_1") (pintype "passive"))
    )
    (net (code "194") (name "/USER_DIP_SW4") (class "Default")
      (node (ref "R419") (pin "1") (pinfunction "1_1") (pintype "passive"))
    )
    (net (code "195") (name "/USER_LED1_BLUE") (class "Default")
      (node (ref "R434") (pin "1") (pinfunction "1_1") (pintype "passive"))
    )
    (net (code "196") (name "/USER_LED1_GREEN") (class "Default")
      (node (ref "R435") (pin "1") (pinfunction "1_1") (pintype "passive"))
    )
    (net (code "197") (name "/USER_LED1_RED") (class "Default")
      (node (ref "R436") (pin "1") (pinfunction "1_1") (pintype "passive"))
    )
    (net (code "198") (name "/USER_LED2_BLUE") (class "Default")
      (node (ref "R437") (pin "1") (pinfunction "1_1") (pintype "passive"))
    )
    (net (code "199") (name "/USER_LED2_GREEN") (class "Default")
      (node (ref "R438") (pin "1") (pinfunction "1_1") (pintype "passive"))
    )
    (net (code "200") (name "/USER_LED2_RED") (class "Default")
      (node (ref "R439") (pin "1") (pinfunction "1_1") (pintype "passive"))
    )
    (net (code "201") (name "DGND") (class "Default")
      (node (ref "CN400") (pin "10") (pinfunction "10_10") (pintype "passive"))
      (node (ref "CN400") (pin "103") (pinfunction "103_103") (pintype "passive"))
      (node (ref "CN400") (pin "104") (pinfunction "104_104") (pintype "passive"))
      (node (ref "CN400") (pin "109") (pinfunction "109_109") (pintype "passive"))
      (node (ref "CN400") (pin "110") (pinfunction "110_110") (pintype "passive"))
      (node (ref "CN400") (pin "115") (pinfunction "115_115") (pintype "passive"))
      (node (ref "CN400") (pin "116") (pinfunction "116_116") (pintype "passive"))
      (node (ref "CN400") (pin "121") (pinfunction "121_121") (pintype "passive"))
      (node (ref "CN400") (pin "122") (pinfunction "122_122") (pintype "passive"))
      (node (ref "CN400") (pin "127") (pinfunction "127_127") (pintype "passive"))
      (node (ref "CN400") (pin "128") (pinfunction "128_128") (pintype "passive"))
      (node (ref "CN400") (pin "13") (pinfunction "13_13") (pintype "passive"))
      (node (ref "CN400") (pin "133") (pinfunction "133_133") (pintype "passive"))
      (node (ref "CN400") (pin "134") (pinfunction "134_134") (pintype "passive"))
      (node (ref "CN400") (pin "139") (pinfunction "139_139") (pintype "passive"))
      (node (ref "CN400") (pin "14") (pinfunction "14_14") (pintype "passive"))
      (node (ref "CN400") (pin "140") (pinfunction "140_140") (pintype "passive"))
      (node (ref "CN400") (pin "145") (pinfunction "145_145") (pintype "passive"))
      (node (ref "CN400") (pin "146") (pinfunction "146_146") (pintype "passive"))
      (node (ref "CN400") (pin "151") (pinfunction "151_151") (pintype "passive"))
      (node (ref "CN400") (pin "152") (pinfunction "152_152") (pintype "passive"))
      (node (ref "CN400") (pin "157") (pinfunction "157_157") (pintype "passive"))
      (node (ref "CN400") (pin "158") (pinfunction "158_158") (pintype "passive"))
      (node (ref "CN400") (pin "163") (pinfunction "163_163") (pintype "passive"))
      (node (ref "CN400") (pin "164") (pinfunction "164_164") (pintype "passive"))
      (node (ref "CN400") (pin "169") (pinfunction "169_169") (pintype "passive"))
      (node (ref "CN400") (pin "170") (pinfunction "170_170") (pintype "passive"))
      (node (ref "CN400") (pin "175") (pinfunction "175_175") (pintype "passive"))
      (node (ref "CN400") (pin "176") (pinfunction "176_176") (pintype "passive"))
      (node (ref "CN400") (pin "181") (pinfunction "181_181") (pintype "passive"))
      (node (ref "CN400") (pin "182") (pinfunction "182_182") (pintype "passive"))
      (node (ref "CN400") (pin "187") (pinfunction "187_187") (pintype "passive"))
      (node (ref "CN400") (pin "188") (pinfunction "188_188") (pintype "passive"))
      (node (ref "CN400") (pin "19") (pinfunction "19_19") (pintype "passive"))
      (node (ref "CN400") (pin "193") (pinfunction "193_193") (pintype "passive"))
      (node (ref "CN400") (pin "194") (pinfunction "194_194") (pintype "passive"))
      (node (ref "CN400") (pin "199") (pinfunction "199_199") (pintype "passive"))
      (node (ref "CN400") (pin "2") (pinfunction "2_2") (pintype "passive"))
      (node (ref "CN400") (pin "20") (pinfunction "20_20") (pintype "passive"))
      (node (ref "CN400") (pin "200") (pinfunction "200_200") (pintype "passive"))
      (node (ref "CN400") (pin "205") (pinfunction "205_205") (pintype "passive"))
      (node (ref "CN400") (pin "206") (pinfunction "206_206") (pintype "passive"))
      (node (ref "CN400") (pin "211") (pinfunction "211_211") (pintype "passive"))
      (node (ref "CN400") (pin "212") (pinfunction "212_212") (pintype "passive"))
      (node (ref "CN400") (pin "217") (pinfunction "217_217") (pintype "passive"))
      (node (ref "CN400") (pin "218") (pinfunction "218_218") (pintype "passive"))
      (node (ref "CN400") (pin "223") (pinfunction "223_223") (pintype "passive"))
      (node (ref "CN400") (pin "224") (pinfunction "224_224") (pintype "passive"))
      (node (ref "CN400") (pin "229") (pinfunction "229_229") (pintype "passive"))
      (node (ref "CN400") (pin "230") (pinfunction "230_230") (pintype "passive"))
      (node (ref "CN400") (pin "235") (pinfunction "235_235") (pintype "passive"))
      (node (ref "CN400") (pin "236") (pinfunction "236_236") (pintype "passive"))
      (node (ref "CN400") (pin "241") (pinfunction "241_241") (pintype "passive"))
      (node (ref "CN400") (pin "242") (pinfunction "242_242") (pintype "passive"))
      (node (ref "CN400") (pin "247") (pinfunction "247_247") (pintype "passive"))
      (node (ref "CN400") (pin "248") (pinfunction "248_248") (pintype "passive"))
      (node (ref "CN400") (pin "25") (pinfunction "25_25") (pintype "passive"))
      (node (ref "CN400") (pin "253") (pinfunction "253_253") (pintype "passive"))
      (node (ref "CN400") (pin "254") (pinfunction "254_254") (pintype "passive"))
      (node (ref "CN400") (pin "259") (pinfunction "259_259") (pintype "passive"))
      (node (ref "CN400") (pin "26") (pinfunction "26_26") (pintype "passive"))
      (node (ref "CN400") (pin "260") (pinfunction "260_260") (pintype "passive"))
      (node (ref "CN400") (pin "31") (pinfunction "31_31") (pintype "passive"))
      (node (ref "CN400") (pin "32") (pinfunction "32_32") (pintype "passive"))
      (node (ref "CN400") (pin "37") (pinfunction "37_37") (pintype "passive"))
      (node (ref "CN400") (pin "38") (pinfunction "38_38") (pintype "passive"))
      (node (ref "CN400") (pin "4") (pinfunction "4_4") (pintype "passive"))
      (node (ref "CN400") (pin "43") (pinfunction "43_43") (pintype "passive"))
      (node (ref "CN400") (pin "44") (pinfunction "44_44") (pintype "passive"))
      (node (ref "CN400") (pin "49") (pinfunction "49_49") (pintype "passive"))
      (node (ref "CN400") (pin "50") (pinfunction "50_50") (pintype "passive"))
      (node (ref "CN400") (pin "55") (pinfunction "55_55") (pintype "passive"))
      (node (ref "CN400") (pin "56") (pinfunction "56_56") (pintype "passive"))
      (node (ref "CN400") (pin "6") (pinfunction "6_6") (pintype "passive"))
      (node (ref "CN400") (pin "61") (pinfunction "61_61") (pintype "passive"))
      (node (ref "CN400") (pin "62") (pinfunction "62_62") (pintype "passive"))
      (node (ref "CN400") (pin "67") (pinfunction "67_67") (pintype "passive"))
      (node (ref "CN400") (pin "68") (pinfunction "68_68") (pintype "passive"))
      (node (ref "CN400") (pin "73") (pinfunction "73_73") (pintype "passive"))
      (node (ref "CN400") (pin "74") (pinfunction "74_74") (pintype "passive"))
      (node (ref "CN400") (pin "79") (pinfunction "79_79") (pintype "passive"))
      (node (ref "CN400") (pin "8") (pinfunction "8_8") (pintype "passive"))
      (node (ref "CN400") (pin "80") (pinfunction "80_80") (pintype "passive"))
      (node (ref "CN400") (pin "85") (pinfunction "85_85") (pintype "passive"))
      (node (ref "CN400") (pin "86") (pinfunction "86_86") (pintype "passive"))
      (node (ref "CN400") (pin "91") (pinfunction "91_91") (pintype "passive"))
      (node (ref "CN400") (pin "92") (pinfunction "92_92") (pintype "passive"))
      (node (ref "CN400") (pin "97") (pinfunction "97_97") (pintype "passive"))
      (node (ref "CN400") (pin "98") (pinfunction "98_98") (pintype "passive"))
    )
    (net (code "202") (name "DP5VS") (class "Default")
      (node (ref "CN400") (pin "1") (pinfunction "1_1") (pintype "passive"))
      (node (ref "CN400") (pin "3") (pinfunction "3_3") (pintype "passive"))
      (node (ref "CN400") (pin "5") (pinfunction "5_5") (pintype "passive"))
      (node (ref "CN400") (pin "7") (pinfunction "7_7") (pintype "passive"))
      (node (ref "CN400") (pin "9") (pinfunction "9_9") (pintype "passive"))
    )
    (net (code "203") (name "unconnected-(CN400-Pad11)") (class "Default")
      (node (ref "CN400") (pin "11") (pinfunction "11_11") (pintype "passive+no_connect"))
    )
    (net (code "204") (name "unconnected-(CN400-Pad12)") (class "Default")
      (node (ref "CN400") (pin "12") (pinfunction "12_12") (pintype "passive+no_connect"))
    )
    (net (code "205") (name "unconnected-(CN400-PadMP)") (class "Default")
      (node (ref "CN400") (pin "MP") (pinfunction "MP_MP") (pintype "passive"))
    )
  )
)
